# PAPR_STM32F030F4_V1.net
KiCad netlist of a schematic drawn in EasyEDA
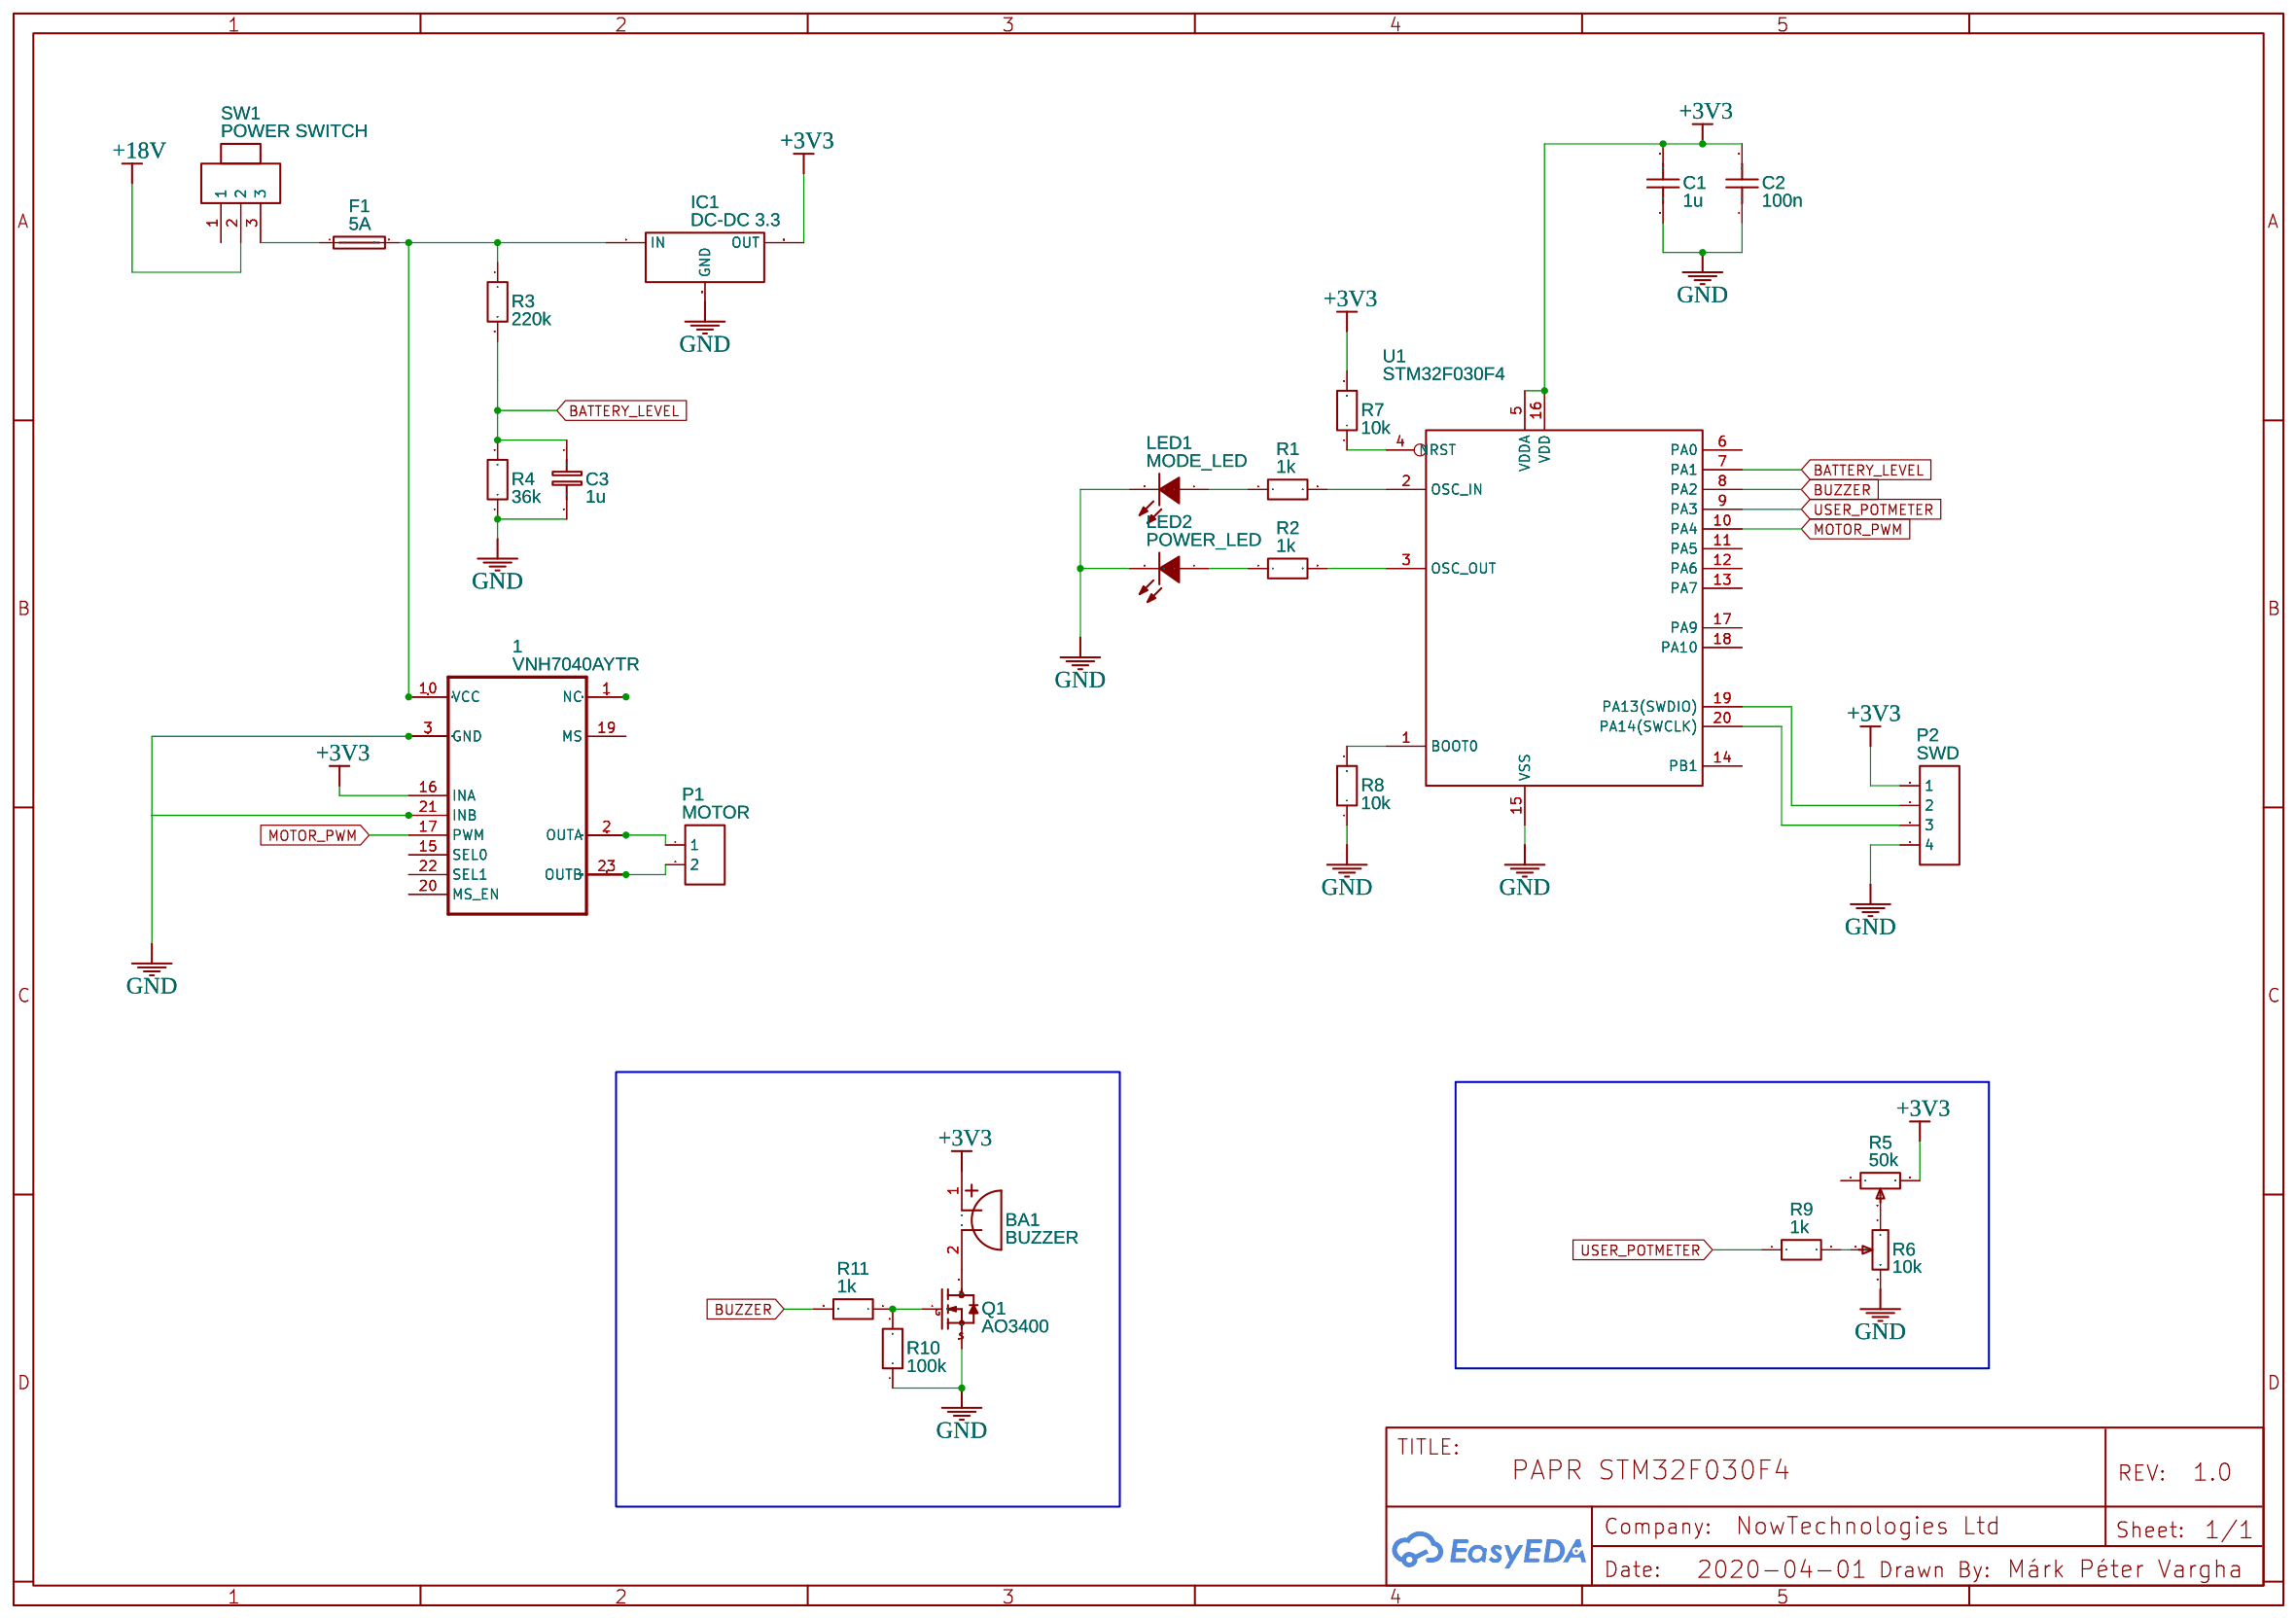
[diagram p0: schematic sheet]

(export (version "E")
  (design (tool "Eeschema 10.0.6"))
  (components
    (comp (ref "1") (value "VNH7040AYTR") (libsource (lib "") (part "VNH7040AYTR")))
    (comp (ref "BA1") (value "BUZZER") (libsource (lib "") (part "9X5.5_BEEPER_5V")))
    (comp (ref "C1") (value "1u") (libsource (lib "") (part "Cap_RAD-0.1_US")))
    (comp (ref "C2") (value "100n") (libsource (lib "") (part "Cap_RAD-0.1_US")))
    (comp (ref "C3") (value "1u") (libsource (lib "") (part "Cap_RAD-0.1_EU")))
    (comp (ref "F1")
      (value "5A")
      (fields
        (field (name "BOM_Manufacturer Part") "5F 5A 250VACGlass tube fuse")
        (field (name "BOM_Supplier Part") "C3120")
      )
      (libsource (lib "") (part "5F 5A 250VACGlass tube fuse"))
    )
    (comp (ref "IC1") (value "DC-DC 3.3") (libsource (lib "") (part "AMS1117 3.3")))
    (comp (ref "LED1")
      (value "MODE_LED")
      (fields
        (field (name "BOM_Manufacturer Part") "204-10SURD/S530-A3")
        (field (name "BOM_Supplier Part") "C99772")
      )
      (libsource (lib "") (part "204-10SURD/S530-A3"))
    )
    (comp (ref "LED2")
      (value "POWER_LED")
      (fields
        (field (name "BOM_Manufacturer Part") "204-10SURD/S530-A3")
        (field (name "BOM_Supplier Part") "C99772")
      )
      (libsource (lib "") (part "204-10SURD/S530-A3"))
    )
    (comp (ref "P1")
      (value "MOTOR")
      (fields
        (field (name "BOM_Manufacturer Part") "2.54-1*2PFemale")
        (field (name "BOM_Supplier Part") "C49661")
      )
      (libsource (lib "") (part "Header-Female-2.54_1x2"))
    )
    (comp (ref "P2") (value "SWD") (libsource (lib "") (part "4P")))
    (comp (ref "Q1")
      (value "AO3400")
      (fields (field (name "BOM_Supplier Part") "C122850"))
      (libsource (lib "") (part "AO3400_C122850"))
    )
    (comp (ref "R1") (value "1k") (libsource (lib "") (part "Res_AXIAL-0.3(1/8W)_EU")))
    (comp (ref "R2") (value "1k") (libsource (lib "") (part "Res_AXIAL-0.3(1/8W)_EU")))
    (comp (ref "R3") (value "220k") (libsource (lib "") (part "Res_AXIAL-0.3(1/8W)_EU_3")))
    (comp (ref "R4") (value "36k") (libsource (lib "") (part "Res_AXIAL-0.3(1/8W)_EU_1")))
    (comp (ref "R5")
      (value "50k")
      (fields
        (field (name "BOM_Manufacturer Part") "3386P-1-101LF")
        (field (name "BOM_Supplier Part") "C125022")
      )
      (libsource (lib "") (part "potmeter"))
    )
    (comp (ref "R6")
      (value "10k")
      (fields
        (field (name "BOM_Manufacturer Part") "3386P-1-101LF")
        (field (name "BOM_Supplier Part") "C125022")
      )
      (libsource (lib "") (part "potmeter_1"))
    )
    (comp (ref "R7") (value "10k") (libsource (lib "") (part "Res_AXIAL-0.3(1/8W)_EU_1")))
    (comp (ref "R8") (value "10k") (libsource (lib "") (part "Res_AXIAL-0.3(1/8W)_EU_1")))
    (comp (ref "R9") (value "1k") (libsource (lib "") (part "Res_AXIAL-0.3(1/8W)_EU")))
    (comp (ref "R10") (value "100k") (libsource (lib "") (part "Res_AXIAL-0.3(1/8W)_EU_1")))
    (comp (ref "R11") (value "1k") (libsource (lib "") (part "Res_AXIAL-0.3(1/8W)_EU_2")))
    (comp (ref "SW1")
      (value "POWER SWITCH")
      (fields
        (field (name "BOM_Manufacturer Part") "Rocker switch601-10211BB")
        (field (name "BOM_Supplier Part") "C67849")
      )
      (libsource (lib "") (part "Rocker switch601-10211BB"))
    )
    (comp (ref "U1") (value "STM32F030F4") (libsource (lib "") (part "STM32F030F4")))
  )
  (nets
    (net (code "1") (name "+3V3") (class "Default")
      (node (ref "1") (pin "16") (pinfunction "INA_16") (pintype "bidirectional"))
      (node (ref "BA1") (pin "1") (pinfunction "1_1") (pintype "unspecified"))
      (node (ref "C1") (pin "2") (pinfunction "2_2") (pintype "unspecified"))
      (node (ref "C2") (pin "2") (pinfunction "2_2") (pintype "unspecified"))
      (node (ref "IC1") (pin "OUT") (pinfunction "OUT_OUT") (pintype "unspecified"))
      (node (ref "P2") (pin "1") (pinfunction "1_1") (pintype "unspecified"))
      (node (ref "R5") (pin "3") (pinfunction "3_3") (pintype "input"))
      (node (ref "R7") (pin "2") (pinfunction "2_2") (pintype "unspecified"))
      (node (ref "U1") (pin "16") (pinfunction "VDD_16") (pintype "unspecified"))
      (node (ref "U1") (pin "5") (pinfunction "VDDA_5") (pintype "unspecified"))
    )
    (net (code "2") (name "+18V") (class "Default")
      (node (ref "SW1") (pin "2") (pinfunction "2_2") (pintype "unspecified"))
    )
    (net (code "3") (name "BATTERY_LEVEL") (class "Default")
      (node (ref "C3") (pin "1") (pinfunction "1_1") (pintype "unspecified"))
      (node (ref "R3") (pin "2") (pinfunction "2_2") (pintype "unspecified"))
      (node (ref "R4") (pin "2") (pinfunction "2_2") (pintype "unspecified"))
      (node (ref "U1") (pin "7") (pinfunction "PA1_7") (pintype "unspecified"))
    )
    (net (code "4") (name "BUZZER") (class "Default")
      (node (ref "R11") (pin "2") (pinfunction "2_2") (pintype "unspecified"))
      (node (ref "U1") (pin "8") (pinfunction "PA2_8") (pintype "unspecified"))
    )
    (net (code "5") (name "GND") (class "Default")
      (node (ref "1") (pin "21") (pinfunction "INB_21") (pintype "bidirectional"))
      (node (ref "1") (pin "3") (pinfunction "GND_3") (pintype "bidirectional"))
      (node (ref "1") (pin "30") (pinfunction "GND_30") (pintype "bidirectional"))
      (node (ref "1") (pin "31") (pinfunction "GND_31") (pintype "bidirectional"))
      (node (ref "1") (pin "32") (pinfunction "GND_32") (pintype "bidirectional"))
      (node (ref "1") (pin "33") (pinfunction "GND_33") (pintype "bidirectional"))
      (node (ref "1") (pin "34") (pinfunction "GND_34") (pintype "bidirectional"))
      (node (ref "1") (pin "4") (pinfunction "GND_4") (pintype "bidirectional"))
      (node (ref "1") (pin "5") (pinfunction "GND_5") (pintype "bidirectional"))
      (node (ref "1") (pin "6") (pinfunction "GND_6") (pintype "bidirectional"))
      (node (ref "1") (pin "7") (pinfunction "GND_7") (pintype "bidirectional"))
      (node (ref "C1") (pin "1") (pinfunction "1_1") (pintype "unspecified"))
      (node (ref "C2") (pin "1") (pinfunction "1_1") (pintype "unspecified"))
      (node (ref "C3") (pin "2") (pinfunction "2_2") (pintype "unspecified"))
      (node (ref "IC1") (pin "GND") (pinfunction "GND_GND") (pintype "input"))
      (node (ref "LED1") (pin "2") (pinfunction "K_2") (pintype "unspecified"))
      (node (ref "LED2") (pin "2") (pinfunction "K_2") (pintype "unspecified"))
      (node (ref "P2") (pin "4") (pinfunction "4_4") (pintype "unspecified"))
      (node (ref "Q1") (pin "2") (pinfunction "S_2") (pintype "unspecified"))
      (node (ref "R10") (pin "1") (pinfunction "1_1") (pintype "unspecified"))
      (node (ref "R4") (pin "1") (pinfunction "1_1") (pintype "unspecified"))
      (node (ref "R6") (pin "3") (pinfunction "3_3") (pintype "input"))
      (node (ref "R8") (pin "1") (pinfunction "1_1") (pintype "unspecified"))
      (node (ref "U1") (pin "15") (pinfunction "VSS_15") (pintype "unspecified"))
    )
    (net (code "6") (name "MOTOR_PWM") (class "Default")
      (node (ref "1") (pin "17") (pinfunction "PWM_17") (pintype "bidirectional"))
      (node (ref "U1") (pin "10") (pinfunction "PA4_10") (pintype "unspecified"))
    )
    (net (code "7") (name "Net-(1-NC-Pad1)") (class "Default")
      (node (ref "1") (pin "1") (pinfunction "NC_1") (pintype "bidirectional"))
      (node (ref "1") (pin "18") (pinfunction "NC_18") (pintype "bidirectional"))
      (node (ref "1") (pin "36") (pinfunction "NC_36") (pintype "bidirectional"))
    )
    (net (code "8") (name "Net-(1-OUTA-Pad11)") (class "Default")
      (node (ref "1") (pin "11") (pinfunction "OUTA_11") (pintype "bidirectional"))
      (node (ref "1") (pin "12") (pinfunction "OUTA_12") (pintype "bidirectional"))
      (node (ref "1") (pin "13") (pinfunction "OUTA_13") (pintype "bidirectional"))
      (node (ref "1") (pin "14") (pinfunction "OUTA_14") (pintype "bidirectional"))
      (node (ref "1") (pin "2") (pinfunction "OUTA_2") (pintype "bidirectional"))
      (node (ref "1") (pin "8") (pinfunction "OUTA_8") (pintype "bidirectional"))
      (node (ref "1") (pin "9") (pinfunction "OUTA_9") (pintype "bidirectional"))
      (node (ref "1") (pin "HS2") (pinfunction "OUTA_HS2") (pintype "bidirectional"))
      (node (ref "P1") (pin "1") (pinfunction "1_1") (pintype "input"))
    )
    (net (code "9") (name "Net-(1-OUTB-Pad23)") (class "Default")
      (node (ref "1") (pin "23") (pinfunction "OUTB_23") (pintype "bidirectional"))
      (node (ref "1") (pin "24") (pinfunction "OUTB_24") (pintype "bidirectional"))
      (node (ref "1") (pin "25") (pinfunction "OUTB_25") (pintype "bidirectional"))
      (node (ref "1") (pin "26") (pinfunction "OUTB_26") (pintype "bidirectional"))
      (node (ref "1") (pin "28") (pinfunction "OUTB_28") (pintype "bidirectional"))
      (node (ref "1") (pin "29") (pinfunction "OUTB_29") (pintype "bidirectional"))
      (node (ref "1") (pin "35") (pinfunction "OUTB_35") (pintype "bidirectional"))
      (node (ref "1") (pin "HS3") (pinfunction "OUTB_HS3") (pintype "bidirectional"))
      (node (ref "P1") (pin "2") (pinfunction "2_2") (pintype "input"))
    )
    (net (code "10") (name "Net-(1-VCC-Pad10)") (class "Default")
      (node (ref "1") (pin "10") (pinfunction "VCC_10") (pintype "bidirectional"))
      (node (ref "1") (pin "27") (pinfunction "VCC_27") (pintype "bidirectional"))
      (node (ref "1") (pin "HS1") (pinfunction "VCC_HS1") (pintype "bidirectional"))
      (node (ref "F1") (pin "2") (pinfunction "2_2") (pintype "unspecified"))
      (node (ref "IC1") (pin "IN") (pinfunction "IN_IN") (pintype "input"))
      (node (ref "R3") (pin "1") (pinfunction "1_1") (pintype "unspecified"))
    )
    (net (code "11") (name "Net-(F1-Pad1)") (class "Default")
      (node (ref "F1") (pin "1") (pinfunction "1_1") (pintype "unspecified"))
      (node (ref "SW1") (pin "3") (pinfunction "3_3") (pintype "unspecified"))
    )
    (net (code "12") (name "Net-(LED1-A)") (class "Default")
      (node (ref "LED1") (pin "1") (pinfunction "A_1") (pintype "unspecified"))
      (node (ref "R1") (pin "1") (pinfunction "1_1") (pintype "unspecified"))
    )
    (net (code "13") (name "Net-(LED2-A)") (class "Default")
      (node (ref "LED2") (pin "1") (pinfunction "A_1") (pintype "unspecified"))
      (node (ref "R2") (pin "1") (pinfunction "1_1") (pintype "unspecified"))
    )
    (net (code "14") (name "Net-(Q1-D)") (class "Default")
      (node (ref "BA1") (pin "2") (pinfunction "2_2") (pintype "unspecified"))
      (node (ref "Q1") (pin "3") (pinfunction "D_3") (pintype "unspecified"))
    )
    (net (code "15") (name "Net-(Q1-G)") (class "Default")
      (node (ref "Q1") (pin "1") (pinfunction "G_1") (pintype "unspecified"))
      (node (ref "R10") (pin "2") (pinfunction "2_2") (pintype "unspecified"))
      (node (ref "R11") (pin "1") (pinfunction "1_1") (pintype "unspecified"))
    )
    (net (code "16") (name "Net-(R5-Pad2)") (class "Default")
      (node (ref "R5") (pin "2") (pinfunction "2_2") (pintype "input"))
      (node (ref "R6") (pin "1") (pinfunction "1_1") (pintype "input"))
    )
    (net (code "17") (name "Net-(R6-Pad2)") (class "Default")
      (node (ref "R6") (pin "2") (pinfunction "2_2") (pintype "input"))
      (node (ref "R9") (pin "2") (pinfunction "2_2") (pintype "unspecified"))
    )
    (net (code "18") (name "Net-(U1-BOOT0)") (class "Default")
      (node (ref "R8") (pin "2") (pinfunction "2_2") (pintype "unspecified"))
      (node (ref "U1") (pin "1") (pinfunction "BOOT0_1") (pintype "unspecified"))
    )
    (net (code "19") (name "Net-(U1-NRST)") (class "Default")
      (node (ref "R7") (pin "1") (pinfunction "1_1") (pintype "unspecified"))
      (node (ref "U1") (pin "4") (pinfunction "NRST_4") (pintype "unspecified"))
    )
    (net (code "20") (name "Net-(U1-OSC_IN)") (class "Default")
      (node (ref "R1") (pin "2") (pinfunction "2_2") (pintype "unspecified"))
      (node (ref "U1") (pin "2") (pinfunction "OSC_IN_2") (pintype "unspecified"))
    )
    (net (code "21") (name "Net-(U1-OSC_OUT)") (class "Default")
      (node (ref "R2") (pin "2") (pinfunction "2_2") (pintype "unspecified"))
      (node (ref "U1") (pin "3") (pinfunction "OSC_OUT_3") (pintype "unspecified"))
    )
    (net (code "22") (name "Net-(U1-PA13(SWDIO))") (class "Default")
      (node (ref "P2") (pin "2") (pinfunction "2_2") (pintype "unspecified"))
      (node (ref "U1") (pin "19") (pinfunction "PA13(SWDIO)_19") (pintype "unspecified"))
    )
    (net (code "23") (name "Net-(U1-PA14(SWCLK))") (class "Default")
      (node (ref "P2") (pin "3") (pinfunction "3_3") (pintype "unspecified"))
      (node (ref "U1") (pin "20") (pinfunction "PA14(SWCLK)_20") (pintype "unspecified"))
    )
    (net (code "24") (name "USER_POTMETER") (class "Default")
      (node (ref "R9") (pin "1") (pinfunction "1_1") (pintype "unspecified"))
      (node (ref "U1") (pin "9") (pinfunction "PA3_9") (pintype "unspecified"))
    )
    (net (code "25") (name "unconnected-(1-MS-Pad19)") (class "Default")
      (node (ref "1") (pin "19") (pinfunction "MS_19") (pintype "bidirectional"))
    )
    (net (code "26") (name "unconnected-(1-MS_EN-Pad20)") (class "Default")
      (node (ref "1") (pin "20") (pinfunction "MS_EN_20") (pintype "bidirectional"))
    )
    (net (code "27") (name "unconnected-(1-SEL0-Pad15)") (class "Default")
      (node (ref "1") (pin "15") (pinfunction "SEL0_15") (pintype "bidirectional"))
    )
    (net (code "28") (name "unconnected-(1-SEL1-Pad22)") (class "Default")
      (node (ref "1") (pin "22") (pinfunction "SEL1_22") (pintype "bidirectional"))
    )
    (net (code "29") (name "unconnected-(R5-Pad1)") (class "Default")
      (node (ref "R5") (pin "1") (pinfunction "1_1") (pintype "input"))
    )
    (net (code "30") (name "unconnected-(SW1-Pad1)") (class "Default")
      (node (ref "SW1") (pin "1") (pinfunction "1_1") (pintype "unspecified"))
    )
    (net (code "31") (name "unconnected-(U1-PA0-Pad6)") (class "Default")
      (node (ref "U1") (pin "6") (pinfunction "PA0_6") (pintype "unspecified"))
    )
    (net (code "32") (name "unconnected-(U1-PA5-Pad11)") (class "Default")
      (node (ref "U1") (pin "11") (pinfunction "PA5_11") (pintype "unspecified"))
    )
    (net (code "33") (name "unconnected-(U1-PA6-Pad12)") (class "Default")
      (node (ref "U1") (pin "12") (pinfunction "PA6_12") (pintype "unspecified"))
    )
    (net (code "34") (name "unconnected-(U1-PA7-Pad13)") (class "Default")
      (node (ref "U1") (pin "13") (pinfunction "PA7_13") (pintype "unspecified"))
    )
    (net (code "35") (name "unconnected-(U1-PA9-Pad17)") (class "Default")
      (node (ref "U1") (pin "17") (pinfunction "PA9_17") (pintype "unspecified"))
    )
    (net (code "36") (name "unconnected-(U1-PA10-Pad18)") (class "Default")
      (node (ref "U1") (pin "18") (pinfunction "PA10_18") (pintype "unspecified"))
    )
    (net (code "37") (name "unconnected-(U1-PB1-Pad14)") (class "Default")
      (node (ref "U1") (pin "14") (pinfunction "PB1_14") (pintype "unspecified"))
    )
  )
)
